# CON_SODIMM_200PIN_MO-224.net
KiCad netlist of a schematic drawn in Altium Designer
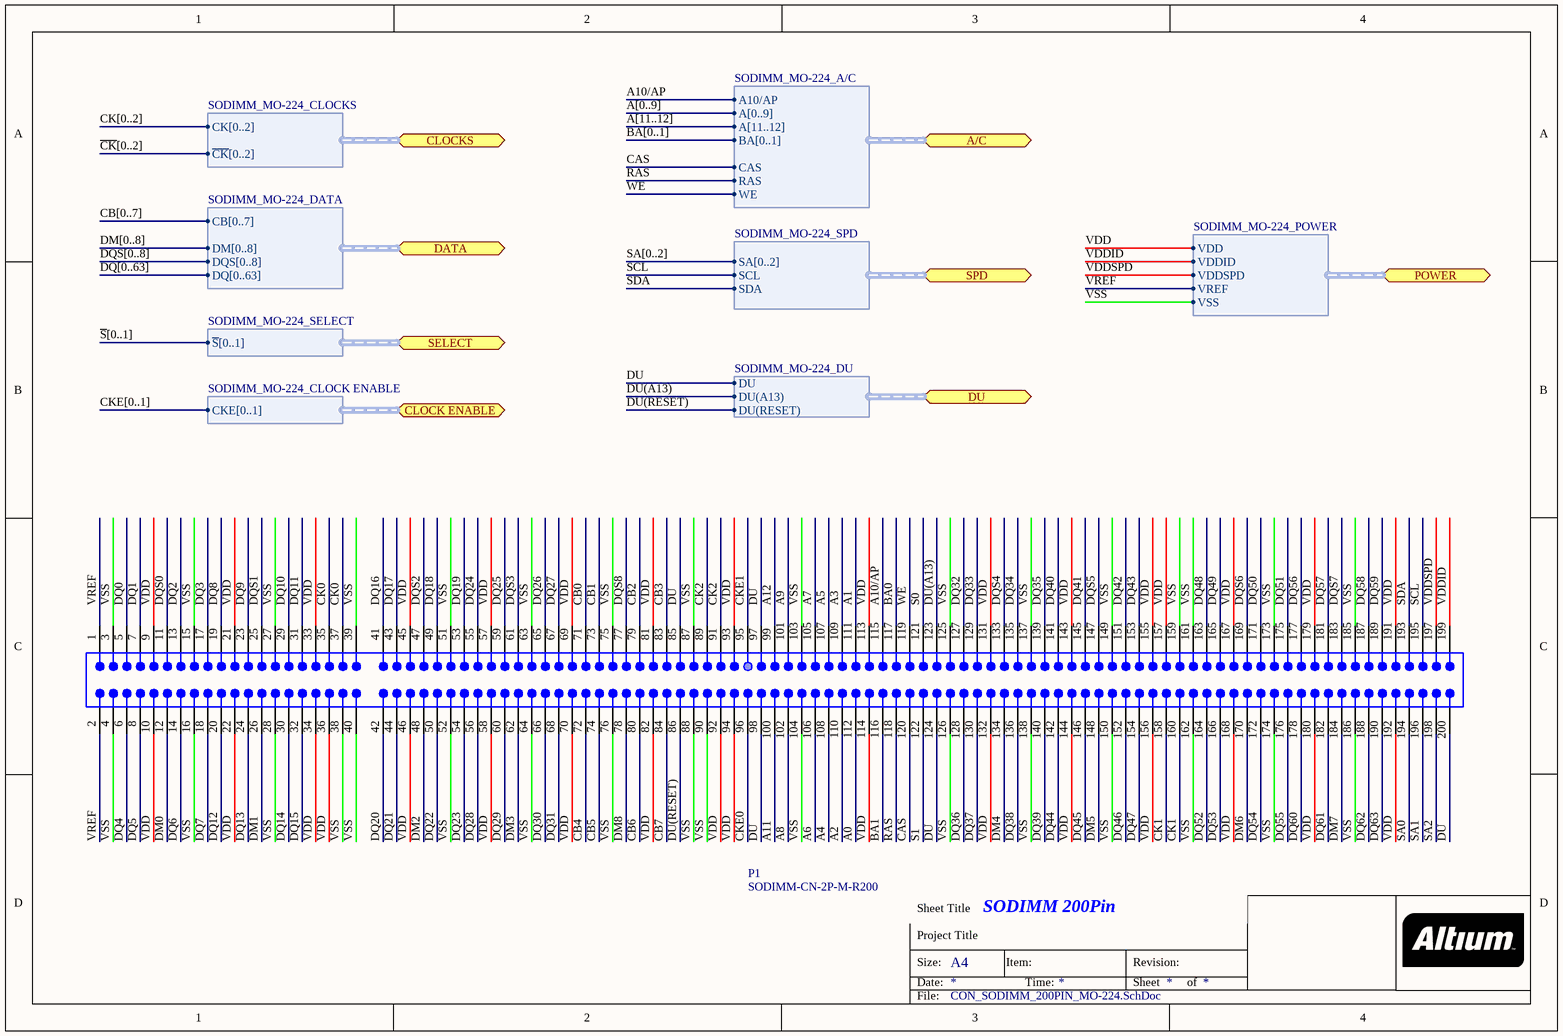
[diagram p0: CON_SODIMM_200PIN_MO-224.SchDoc]

(export (version "E")
  (design (tool "Eeschema 10.0.6"))
  (components
    (comp (ref "P1")
      (value "SODIMM-CN-2P-M-R200")
      (footprint "SODIMM-GF-2D-600-1K-S200")
      (description "Golden finger, SODIMM, Dual, Staggered, Pitch 0.6mm, 200-Position")
      (fields (field (name "PUBLISHER") "Altium"))
      (libsource (lib "Altium Shanghai") (part "CMP-0001-00060-2"))
    )
  )
  (nets
    (net (code "10") (name "/A0") (class "Default")
      (node (ref "P1") (pin "112") (pinfunction "112_112") (pintype "passive"))
    )
    (net (code "11") (name "/A1") (class "Default")
      (node (ref "P1") (pin "111") (pinfunction "111_111") (pintype "passive"))
    )
    (net (code "12") (name "/A2") (class "Default")
      (node (ref "P1") (pin "110") (pinfunction "110_110") (pintype "passive"))
    )
    (net (code "13") (name "/A3") (class "Default")
      (node (ref "P1") (pin "109") (pinfunction "109_109") (pintype "passive"))
    )
    (net (code "14") (name "/A4") (class "Default")
      (node (ref "P1") (pin "108") (pinfunction "108_108") (pintype "passive"))
    )
    (net (code "15") (name "/A5") (class "Default")
      (node (ref "P1") (pin "107") (pinfunction "107_107") (pintype "passive"))
    )
    (net (code "16") (name "/A6") (class "Default")
      (node (ref "P1") (pin "106") (pinfunction "106_106") (pintype "passive"))
    )
    (net (code "17") (name "/A7") (class "Default")
      (node (ref "P1") (pin "105") (pinfunction "105_105") (pintype "passive"))
    )
    (net (code "18") (name "/A8") (class "Default")
      (node (ref "P1") (pin "102") (pinfunction "102_102") (pintype "passive"))
    )
    (net (code "19") (name "/A9") (class "Default")
      (node (ref "P1") (pin "101") (pinfunction "101_101") (pintype "passive"))
    )
    (net (code "20") (name "/A10{slash}AP") (class "Default")
      (node (ref "P1") (pin "115") (pinfunction "115_115") (pintype "passive"))
    )
    (net (code "21") (name "/A11") (class "Default")
      (node (ref "P1") (pin "100") (pinfunction "100_100") (pintype "passive"))
    )
    (net (code "22") (name "/A12") (class "Default")
      (node (ref "P1") (pin "99") (pinfunction "99_99") (pintype "passive"))
    )
    (net (code "25") (name "/BA0") (class "Default")
      (node (ref "P1") (pin "117") (pinfunction "117_117") (pintype "passive"))
    )
    (net (code "26") (name "/BA1") (class "Default")
      (node (ref "P1") (pin "116") (pinfunction "116_116") (pintype "passive"))
    )
    (net (code "28") (name "/CAS") (class "Default")
      (node (ref "P1") (pin "120") (pinfunction "120_120") (pintype "passive"))
    )
    (net (code "29") (name "/CB0") (class "Default")
      (node (ref "P1") (pin "71") (pinfunction "71_71") (pintype "passive"))
    )
    (net (code "30") (name "/CB1") (class "Default")
      (node (ref "P1") (pin "73") (pinfunction "73_73") (pintype "passive"))
    )
    (net (code "31") (name "/CB2") (class "Default")
      (node (ref "P1") (pin "79") (pinfunction "79_79") (pintype "passive"))
    )
    (net (code "32") (name "/CB3") (class "Default")
      (node (ref "P1") (pin "83") (pinfunction "83_83") (pintype "passive"))
    )
    (net (code "33") (name "/CB4") (class "Default")
      (node (ref "P1") (pin "72") (pinfunction "72_72") (pintype "passive"))
    )
    (net (code "34") (name "/CB5") (class "Default")
      (node (ref "P1") (pin "74") (pinfunction "74_74") (pintype "passive"))
    )
    (net (code "35") (name "/CB6") (class "Default")
      (node (ref "P1") (pin "80") (pinfunction "80_80") (pintype "passive"))
    )
    (net (code "36") (name "/CB7") (class "Default")
      (node (ref "P1") (pin "84") (pinfunction "84_84") (pintype "passive"))
    )
    (net (code "38") (name "/CK0") (class "Default")
      (node (ref "P1") (pin "35") (pinfunction "35_35") (pintype "passive"))
    )
    (net (code "39") (name "/CK1") (class "Default")
      (node (ref "P1") (pin "160") (pinfunction "160_160") (pintype "passive"))
    )
    (net (code "40") (name "/CK2") (class "Default")
      (node (ref "P1") (pin "89") (pinfunction "89_89") (pintype "passive"))
    )
    (net (code "41") (name "/CKE0") (class "Default")
      (node (ref "P1") (pin "96") (pinfunction "96_96") (pintype "passive"))
    )
    (net (code "42") (name "/CKE1") (class "Default")
      (node (ref "P1") (pin "95") (pinfunction "95_95") (pintype "passive"))
    )
    (net (code "45") (name "/DM0") (class "Default")
      (node (ref "P1") (pin "12") (pinfunction "12_12") (pintype "passive"))
    )
    (net (code "46") (name "/DM1") (class "Default")
      (node (ref "P1") (pin "26") (pinfunction "26_26") (pintype "passive"))
    )
    (net (code "47") (name "/DM2") (class "Default")
      (node (ref "P1") (pin "48") (pinfunction "48_48") (pintype "passive"))
    )
    (net (code "48") (name "/DM3") (class "Default")
      (node (ref "P1") (pin "62") (pinfunction "62_62") (pintype "passive"))
    )
    (net (code "49") (name "/DM4") (class "Default")
      (node (ref "P1") (pin "134") (pinfunction "134_134") (pintype "passive"))
    )
    (net (code "50") (name "/DM5") (class "Default")
      (node (ref "P1") (pin "148") (pinfunction "148_148") (pintype "passive"))
    )
    (net (code "51") (name "/DM6") (class "Default")
      (node (ref "P1") (pin "170") (pinfunction "170_170") (pintype "passive"))
    )
    (net (code "52") (name "/DM7") (class "Default")
      (node (ref "P1") (pin "184") (pinfunction "184_184") (pintype "passive"))
    )
    (net (code "53") (name "/DM8") (class "Default")
      (node (ref "P1") (pin "78") (pinfunction "78_78") (pintype "passive"))
    )
    (net (code "55") (name "/DQ0") (class "Default")
      (node (ref "P1") (pin "5") (pinfunction "5_5") (pintype "passive"))
    )
    (net (code "56") (name "/DQ1") (class "Default")
      (node (ref "P1") (pin "7") (pinfunction "7_7") (pintype "passive"))
    )
    (net (code "57") (name "/DQ2") (class "Default")
      (node (ref "P1") (pin "13") (pinfunction "13_13") (pintype "passive"))
    )
    (net (code "58") (name "/DQ3") (class "Default")
      (node (ref "P1") (pin "17") (pinfunction "17_17") (pintype "passive"))
    )
    (net (code "59") (name "/DQ4") (class "Default")
      (node (ref "P1") (pin "6") (pinfunction "6_6") (pintype "passive"))
    )
    (net (code "60") (name "/DQ5") (class "Default")
      (node (ref "P1") (pin "8") (pinfunction "8_8") (pintype "passive"))
    )
    (net (code "61") (name "/DQ6") (class "Default")
      (node (ref "P1") (pin "14") (pinfunction "14_14") (pintype "passive"))
    )
    (net (code "62") (name "/DQ7") (class "Default")
      (node (ref "P1") (pin "18") (pinfunction "18_18") (pintype "passive"))
    )
    (net (code "63") (name "/DQ8") (class "Default")
      (node (ref "P1") (pin "19") (pinfunction "19_19") (pintype "passive"))
    )
    (net (code "64") (name "/DQ9") (class "Default")
      (node (ref "P1") (pin "23") (pinfunction "23_23") (pintype "passive"))
    )
    (net (code "65") (name "/DQ10") (class "Default")
      (node (ref "P1") (pin "29") (pinfunction "29_29") (pintype "passive"))
    )
    (net (code "66") (name "/DQ11") (class "Default")
      (node (ref "P1") (pin "31") (pinfunction "31_31") (pintype "passive"))
    )
    (net (code "67") (name "/DQ12") (class "Default")
      (node (ref "P1") (pin "20") (pinfunction "20_20") (pintype "passive"))
    )
    (net (code "68") (name "/DQ13") (class "Default")
      (node (ref "P1") (pin "24") (pinfunction "24_24") (pintype "passive"))
    )
    (net (code "69") (name "/DQ14") (class "Default")
      (node (ref "P1") (pin "30") (pinfunction "30_30") (pintype "passive"))
    )
    (net (code "70") (name "/DQ15") (class "Default")
      (node (ref "P1") (pin "32") (pinfunction "32_32") (pintype "passive"))
    )
    (net (code "71") (name "/DQ16") (class "Default")
      (node (ref "P1") (pin "41") (pinfunction "41_41") (pintype "passive"))
    )
    (net (code "72") (name "/DQ17") (class "Default")
      (node (ref "P1") (pin "43") (pinfunction "43_43") (pintype "passive"))
    )
    (net (code "73") (name "/DQ18") (class "Default")
      (node (ref "P1") (pin "49") (pinfunction "49_49") (pintype "passive"))
    )
    (net (code "74") (name "/DQ19") (class "Default")
      (node (ref "P1") (pin "53") (pinfunction "53_53") (pintype "passive"))
    )
    (net (code "75") (name "/DQ20") (class "Default")
      (node (ref "P1") (pin "42") (pinfunction "42_42") (pintype "passive"))
    )
    (net (code "76") (name "/DQ21") (class "Default")
      (node (ref "P1") (pin "44") (pinfunction "44_44") (pintype "passive"))
    )
    (net (code "77") (name "/DQ22") (class "Default")
      (node (ref "P1") (pin "50") (pinfunction "50_50") (pintype "passive"))
    )
    (net (code "78") (name "/DQ23") (class "Default")
      (node (ref "P1") (pin "54") (pinfunction "54_54") (pintype "passive"))
    )
    (net (code "79") (name "/DQ24") (class "Default")
      (node (ref "P1") (pin "55") (pinfunction "55_55") (pintype "passive"))
    )
    (net (code "80") (name "/DQ25") (class "Default")
      (node (ref "P1") (pin "59") (pinfunction "59_59") (pintype "passive"))
    )
    (net (code "81") (name "/DQ26") (class "Default")
      (node (ref "P1") (pin "65") (pinfunction "65_65") (pintype "passive"))
    )
    (net (code "82") (name "/DQ27") (class "Default")
      (node (ref "P1") (pin "67") (pinfunction "67_67") (pintype "passive"))
    )
    (net (code "83") (name "/DQ28") (class "Default")
      (node (ref "P1") (pin "56") (pinfunction "56_56") (pintype "passive"))
    )
    (net (code "84") (name "/DQ29") (class "Default")
      (node (ref "P1") (pin "60") (pinfunction "60_60") (pintype "passive"))
    )
    (net (code "85") (name "/DQ30") (class "Default")
      (node (ref "P1") (pin "66") (pinfunction "66_66") (pintype "passive"))
    )
    (net (code "86") (name "/DQ31") (class "Default")
      (node (ref "P1") (pin "68") (pinfunction "68_68") (pintype "passive"))
    )
    (net (code "87") (name "/DQ32") (class "Default")
      (node (ref "P1") (pin "127") (pinfunction "127_127") (pintype "passive"))
    )
    (net (code "88") (name "/DQ33") (class "Default")
      (node (ref "P1") (pin "129") (pinfunction "129_129") (pintype "passive"))
    )
    (net (code "89") (name "/DQ34") (class "Default")
      (node (ref "P1") (pin "135") (pinfunction "135_135") (pintype "passive"))
    )
    (net (code "90") (name "/DQ35") (class "Default")
      (node (ref "P1") (pin "139") (pinfunction "139_139") (pintype "passive"))
    )
    (net (code "91") (name "/DQ36") (class "Default")
      (node (ref "P1") (pin "128") (pinfunction "128_128") (pintype "passive"))
    )
    (net (code "92") (name "/DQ37") (class "Default")
      (node (ref "P1") (pin "130") (pinfunction "130_130") (pintype "passive"))
    )
    (net (code "93") (name "/DQ38") (class "Default")
      (node (ref "P1") (pin "136") (pinfunction "136_136") (pintype "passive"))
    )
    (net (code "94") (name "/DQ39") (class "Default")
      (node (ref "P1") (pin "140") (pinfunction "140_140") (pintype "passive"))
    )
    (net (code "95") (name "/DQ40") (class "Default")
      (node (ref "P1") (pin "141") (pinfunction "141_141") (pintype "passive"))
    )
    (net (code "96") (name "/DQ41") (class "Default")
      (node (ref "P1") (pin "145") (pinfunction "145_145") (pintype "passive"))
    )
    (net (code "97") (name "/DQ42") (class "Default")
      (node (ref "P1") (pin "151") (pinfunction "151_151") (pintype "passive"))
    )
    (net (code "98") (name "/DQ43") (class "Default")
      (node (ref "P1") (pin "153") (pinfunction "153_153") (pintype "passive"))
    )
    (net (code "99") (name "/DQ44") (class "Default")
      (node (ref "P1") (pin "142") (pinfunction "142_142") (pintype "passive"))
    )
    (net (code "100") (name "/DQ45") (class "Default")
      (node (ref "P1") (pin "146") (pinfunction "146_146") (pintype "passive"))
    )
    (net (code "101") (name "/DQ46") (class "Default")
      (node (ref "P1") (pin "152") (pinfunction "152_152") (pintype "passive"))
    )
    (net (code "102") (name "/DQ47") (class "Default")
      (node (ref "P1") (pin "154") (pinfunction "154_154") (pintype "passive"))
    )
    (net (code "103") (name "/DQ48") (class "Default")
      (node (ref "P1") (pin "163") (pinfunction "163_163") (pintype "passive"))
    )
    (net (code "104") (name "/DQ49") (class "Default")
      (node (ref "P1") (pin "165") (pinfunction "165_165") (pintype "passive"))
    )
    (net (code "105") (name "/DQ50") (class "Default")
      (node (ref "P1") (pin "171") (pinfunction "171_171") (pintype "passive"))
    )
    (net (code "106") (name "/DQ51") (class "Default")
      (node (ref "P1") (pin "175") (pinfunction "175_175") (pintype "passive"))
    )
    (net (code "107") (name "/DQ52") (class "Default")
      (node (ref "P1") (pin "164") (pinfunction "164_164") (pintype "passive"))
    )
    (net (code "108") (name "/DQ53") (class "Default")
      (node (ref "P1") (pin "166") (pinfunction "166_166") (pintype "passive"))
    )
    (net (code "109") (name "/DQ54") (class "Default")
      (node (ref "P1") (pin "172") (pinfunction "172_172") (pintype "passive"))
    )
    (net (code "110") (name "/DQ55") (class "Default")
      (node (ref "P1") (pin "176") (pinfunction "176_176") (pintype "passive"))
    )
    (net (code "111") (name "/DQ56") (class "Default")
      (node (ref "P1") (pin "177") (pinfunction "177_177") (pintype "passive"))
    )
    (net (code "112") (name "/DQ57") (class "Default")
      (node (ref "P1") (pin "181") (pinfunction "181_181") (pintype "passive"))
    )
    (net (code "113") (name "/DQ58") (class "Default")
      (node (ref "P1") (pin "187") (pinfunction "187_187") (pintype "passive"))
    )
    (net (code "114") (name "/DQ59") (class "Default")
      (node (ref "P1") (pin "189") (pinfunction "189_189") (pintype "passive"))
    )
    (net (code "115") (name "/DQ60") (class "Default")
      (node (ref "P1") (pin "178") (pinfunction "178_178") (pintype "passive"))
    )
    (net (code "116") (name "/DQ61") (class "Default")
      (node (ref "P1") (pin "182") (pinfunction "182_182") (pintype "passive"))
    )
    (net (code "117") (name "/DQ62") (class "Default")
      (node (ref "P1") (pin "188") (pinfunction "188_188") (pintype "passive"))
    )
    (net (code "118") (name "/DQ63") (class "Default")
      (node (ref "P1") (pin "190") (pinfunction "190_190") (pintype "passive"))
    )
    (net (code "119") (name "/DQS0") (class "Default")
      (node (ref "P1") (pin "11") (pinfunction "11_11") (pintype "passive"))
    )
    (net (code "120") (name "/DQS1") (class "Default")
      (node (ref "P1") (pin "25") (pinfunction "25_25") (pintype "passive"))
    )
    (net (code "121") (name "/DQS2") (class "Default")
      (node (ref "P1") (pin "47") (pinfunction "47_47") (pintype "passive"))
    )
    (net (code "122") (name "/DQS3") (class "Default")
      (node (ref "P1") (pin "61") (pinfunction "61_61") (pintype "passive"))
    )
    (net (code "123") (name "/DQS4") (class "Default")
      (node (ref "P1") (pin "133") (pinfunction "133_133") (pintype "passive"))
    )
    (net (code "124") (name "/DQS5") (class "Default")
      (node (ref "P1") (pin "147") (pinfunction "147_147") (pintype "passive"))
    )
    (net (code "125") (name "/DQS6") (class "Default")
      (node (ref "P1") (pin "169") (pinfunction "169_169") (pintype "passive"))
    )
    (net (code "126") (name "/DQS7") (class "Default")
      (node (ref "P1") (pin "183") (pinfunction "183_183") (pintype "passive"))
    )
    (net (code "127") (name "/DQS8") (class "Default")
      (node (ref "P1") (pin "77") (pinfunction "77_77") (pintype "passive"))
    )
    (net (code "130") (name "/DU") (class "Default")
      (node (ref "P1") (pin "124") (pinfunction "124_124") (pintype "passive"))
      (node (ref "P1") (pin "200") (pinfunction "200_200") (pintype "passive"))
      (node (ref "P1") (pin "85") (pinfunction "85_85") (pintype "passive"))
      (node (ref "P1") (pin "97") (pinfunction "97_97") (pintype "passive"))
      (node (ref "P1") (pin "98") (pinfunction "98_98") (pintype "passive"))
    )
    (net (code "131") (name "/DU(A13)") (class "Default")
      (node (ref "P1") (pin "123") (pinfunction "123_123") (pintype "passive"))
    )
    (net (code "132") (name "/DU(RESET)") (class "Default")
      (node (ref "P1") (pin "86") (pinfunction "86_86") (pintype "passive"))
    )
    (net (code "133") (name "/RAS") (class "Default")
      (node (ref "P1") (pin "118") (pinfunction "118_118") (pintype "passive"))
    )
    (net (code "134") (name "/SA0") (class "Default")
      (node (ref "P1") (pin "194") (pinfunction "194_194") (pintype "passive"))
    )
    (net (code "135") (name "/SA1") (class "Default")
      (node (ref "P1") (pin "196") (pinfunction "196_196") (pintype "passive"))
    )
    (net (code "136") (name "/SA2") (class "Default")
      (node (ref "P1") (pin "198") (pinfunction "198_198") (pintype "passive"))
    )
    (net (code "138") (name "/SCL") (class "Default")
      (node (ref "P1") (pin "195") (pinfunction "195_195") (pintype "passive"))
    )
    (net (code "139") (name "/SDA") (class "Default")
      (node (ref "P1") (pin "193") (pinfunction "193_193") (pintype "passive"))
    )
    (net (code "140") (name "/VDD") (class "Default")
      (node (ref "P1") (pin "10") (pinfunction "10_10") (pintype "passive"))
      (node (ref "P1") (pin "113") (pinfunction "113_113") (pintype "passive"))
      (node (ref "P1") (pin "114") (pinfunction "114_114") (pintype "passive"))
      (node (ref "P1") (pin "131") (pinfunction "131_131") (pintype "passive"))
      (node (ref "P1") (pin "132") (pinfunction "132_132") (pintype "passive"))
      (node (ref "P1") (pin "143") (pinfunction "143_143") (pintype "passive"))
      (node (ref "P1") (pin "144") (pinfunction "144_144") (pintype "passive"))
      (node (ref "P1") (pin "155") (pinfunction "155_155") (pintype "passive"))
      (node (ref "P1") (pin "156") (pinfunction "156_156") (pintype "passive"))
      (node (ref "P1") (pin "157") (pinfunction "157_157") (pintype "passive"))
      (node (ref "P1") (pin "167") (pinfunction "167_167") (pintype "passive"))
      (node (ref "P1") (pin "168") (pinfunction "168_168") (pintype "passive"))
      (node (ref "P1") (pin "179") (pinfunction "179_179") (pintype "passive"))
      (node (ref "P1") (pin "180") (pinfunction "180_180") (pintype "passive"))
      (node (ref "P1") (pin "191") (pinfunction "191_191") (pintype "passive"))
      (node (ref "P1") (pin "192") (pinfunction "192_192") (pintype "passive"))
      (node (ref "P1") (pin "21") (pinfunction "21_21") (pintype "passive"))
      (node (ref "P1") (pin "22") (pinfunction "22_22") (pintype "passive"))
      (node (ref "P1") (pin "33") (pinfunction "33_33") (pintype "passive"))
      (node (ref "P1") (pin "34") (pinfunction "34_34") (pintype "passive"))
      (node (ref "P1") (pin "36") (pinfunction "36_36") (pintype "passive"))
      (node (ref "P1") (pin "45") (pinfunction "45_45") (pintype "passive"))
      (node (ref "P1") (pin "46") (pinfunction "46_46") (pintype "passive"))
      (node (ref "P1") (pin "57") (pinfunction "57_57") (pintype "passive"))
      (node (ref "P1") (pin "58") (pinfunction "58_58") (pintype "passive"))
      (node (ref "P1") (pin "69") (pinfunction "69_69") (pintype "passive"))
      (node (ref "P1") (pin "70") (pinfunction "70_70") (pintype "passive"))
      (node (ref "P1") (pin "81") (pinfunction "81_81") (pintype "passive"))
      (node (ref "P1") (pin "82") (pinfunction "82_82") (pintype "passive"))
      (node (ref "P1") (pin "9") (pinfunction "9_9") (pintype "passive"))
      (node (ref "P1") (pin "92") (pinfunction "92_92") (pintype "passive"))
      (node (ref "P1") (pin "93") (pinfunction "93_93") (pintype "passive"))
      (node (ref "P1") (pin "94") (pinfunction "94_94") (pintype "passive"))
    )
    (net (code "141") (name "/VDDID") (class "Default")
      (node (ref "P1") (pin "199") (pinfunction "199_199") (pintype "passive"))
    )
    (net (code "142") (name "/VDDSPD") (class "Default")
      (node (ref "P1") (pin "197") (pinfunction "197_197") (pintype "passive"))
    )
    (net (code "143") (name "/VREF") (class "Default")
      (node (ref "P1") (pin "1") (pinfunction "1_1") (pintype "passive"))
      (node (ref "P1") (pin "2") (pinfunction "2_2") (pintype "passive"))
    )
    (net (code "144") (name "/VSS") (class "Default")
      (node (ref "P1") (pin "103") (pinfunction "103_103") (pintype "passive"))
      (node (ref "P1") (pin "104") (pinfunction "104_104") (pintype "passive"))
      (node (ref "P1") (pin "125") (pinfunction "125_125") (pintype "passive"))
      (node (ref "P1") (pin "126") (pinfunction "126_126") (pintype "passive"))
      (node (ref "P1") (pin "137") (pinfunction "137_137") (pintype "passive"))
      (node (ref "P1") (pin "138") (pinfunction "138_138") (pintype "passive"))
      (node (ref "P1") (pin "149") (pinfunction "149_149") (pintype "passive"))
      (node (ref "P1") (pin "15") (pinfunction "15_15") (pintype "passive"))
      (node (ref "P1") (pin "150") (pinfunction "150_150") (pintype "passive"))
      (node (ref "P1") (pin "159") (pinfunction "159_159") (pintype "passive"))
      (node (ref "P1") (pin "16") (pinfunction "16_16") (pintype "passive"))
      (node (ref "P1") (pin "161") (pinfunction "161_161") (pintype "passive"))
      (node (ref "P1") (pin "162") (pinfunction "162_162") (pintype "passive"))
      (node (ref "P1") (pin "173") (pinfunction "173_173") (pintype "passive"))
      (node (ref "P1") (pin "174") (pinfunction "174_174") (pintype "passive"))
      (node (ref "P1") (pin "185") (pinfunction "185_185") (pintype "passive"))
      (node (ref "P1") (pin "186") (pinfunction "186_186") (pintype "passive"))
      (node (ref "P1") (pin "27") (pinfunction "27_27") (pintype "passive"))
      (node (ref "P1") (pin "28") (pinfunction "28_28") (pintype "passive"))
      (node (ref "P1") (pin "3") (pinfunction "3_3") (pintype "passive"))
      (node (ref "P1") (pin "38") (pinfunction "38_38") (pintype "passive"))
      (node (ref "P1") (pin "39") (pinfunction "39_39") (pintype "passive"))
      (node (ref "P1") (pin "4") (pinfunction "4_4") (pintype "passive"))
      (node (ref "P1") (pin "40") (pinfunction "40_40") (pintype "passive"))
      (node (ref "P1") (pin "51") (pinfunction "51_51") (pintype "passive"))
      (node (ref "P1") (pin "52") (pinfunction "52_52") (pintype "passive"))
      (node (ref "P1") (pin "63") (pinfunction "63_63") (pintype "passive"))
      (node (ref "P1") (pin "64") (pinfunction "64_64") (pintype "passive"))
      (node (ref "P1") (pin "75") (pinfunction "75_75") (pintype "passive"))
      (node (ref "P1") (pin "76") (pinfunction "76_76") (pintype "passive"))
      (node (ref "P1") (pin "87") (pinfunction "87_87") (pintype "passive"))
      (node (ref "P1") (pin "88") (pinfunction "88_88") (pintype "passive"))
      (node (ref "P1") (pin "90") (pinfunction "90_90") (pintype "passive"))
    )
    (net (code "145") (name "/WE") (class "Default")
      (node (ref "P1") (pin "119") (pinfunction "119_119") (pintype "passive"))
    )
    (net (code "154") (name "/~{CK}0") (class "Default")
      (node (ref "P1") (pin "37") (pinfunction "37_37") (pintype "passive"))
    )
    (net (code "155") (name "/~{CK}1") (class "Default")
      (node (ref "P1") (pin "158") (pinfunction "158_158") (pintype "passive"))
    )
    (net (code "156") (name "/~{CK}2") (class "Default")
      (node (ref "P1") (pin "91") (pinfunction "91_91") (pintype "passive"))
    )
    (net (code "158") (name "/~{S}0") (class "Default")
      (node (ref "P1") (pin "121") (pinfunction "121_121") (pintype "passive"))
    )
    (net (code "159") (name "/~{S}1") (class "Default")
      (node (ref "P1") (pin "122") (pinfunction "122_122") (pintype "passive"))
    )
  )
)
